# Pipa_PRD.net
KiCad netlist of a schematic drawn in Altium Designer
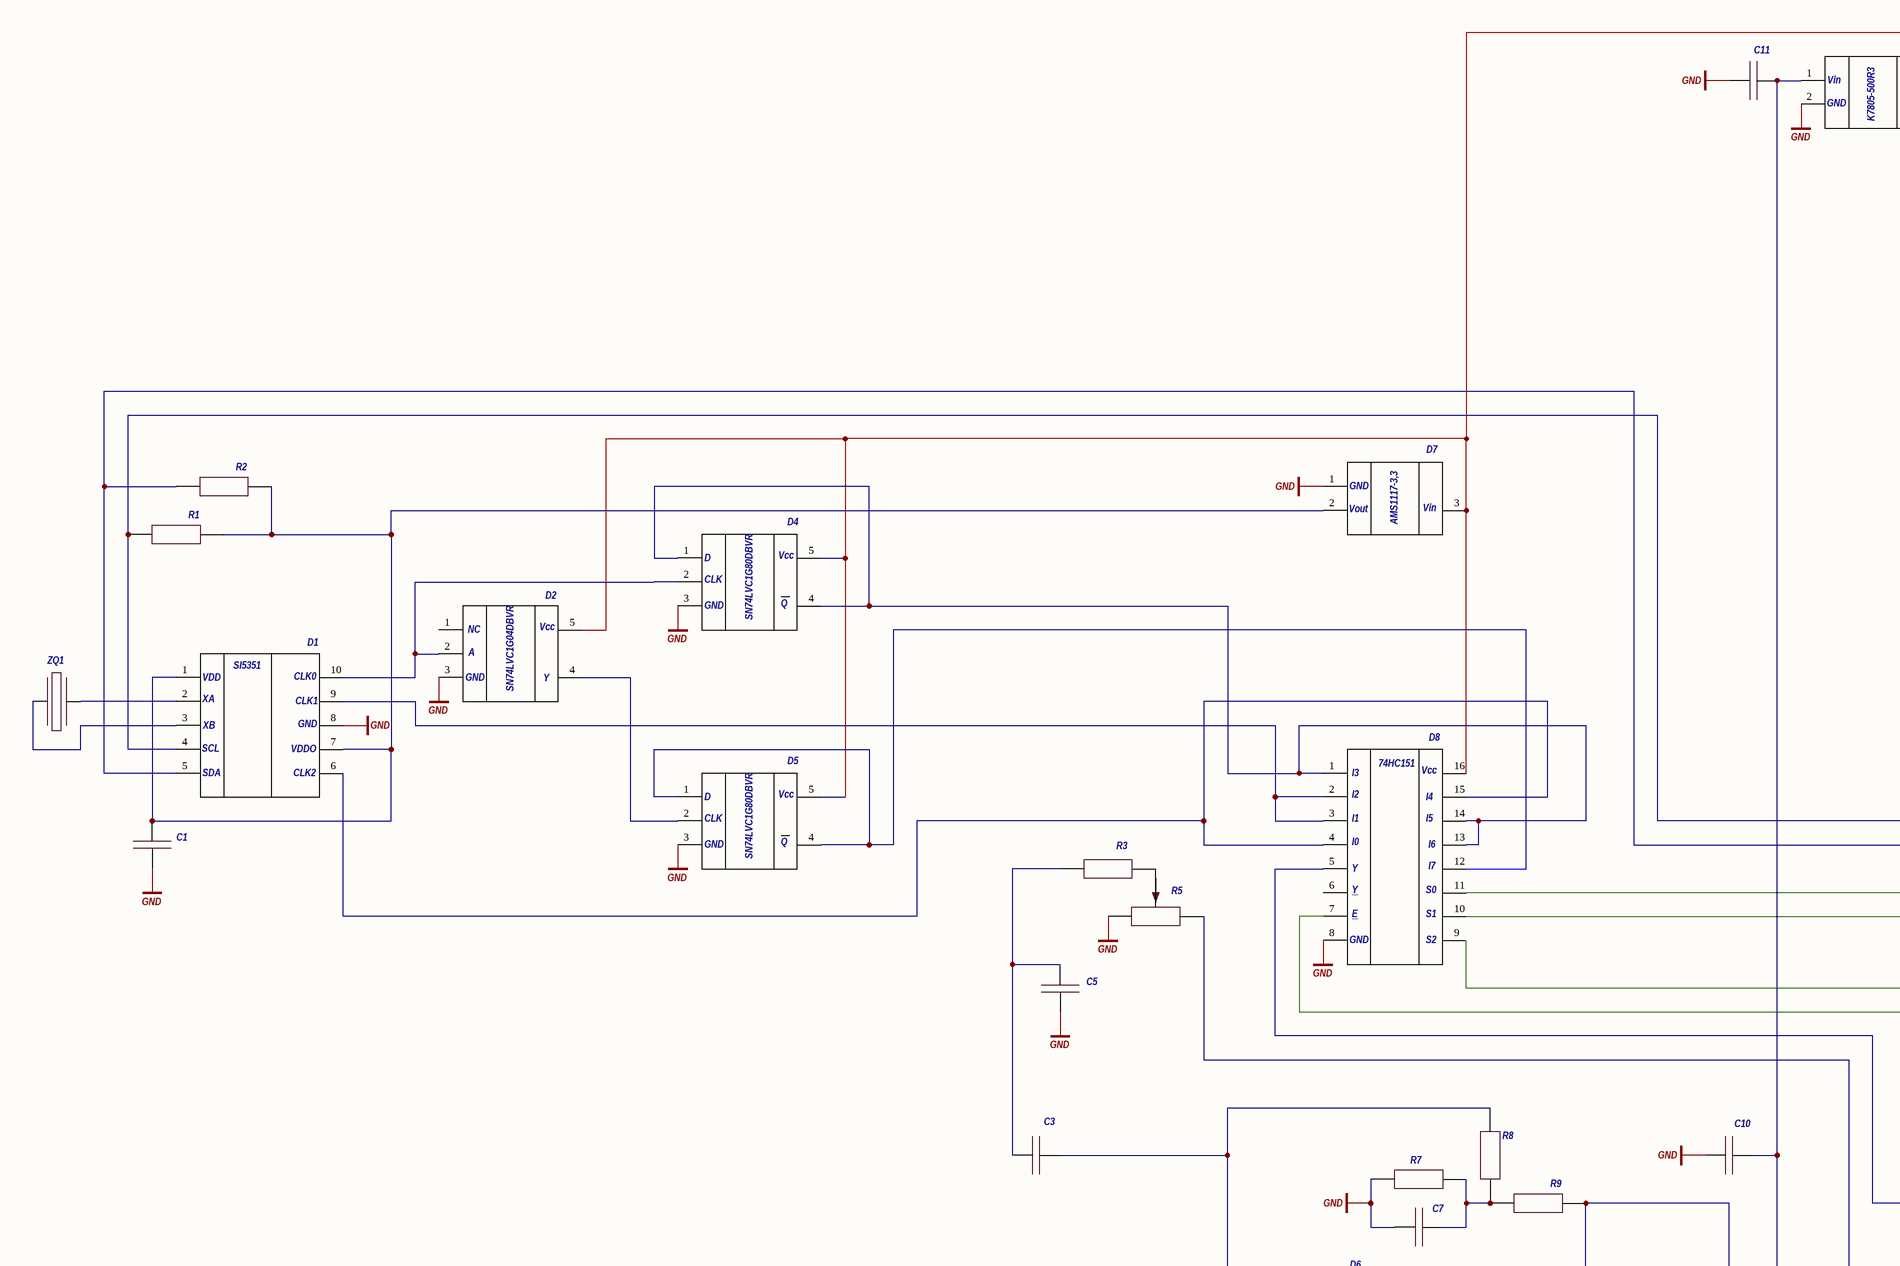
[diagram p0: Pipa PRD.SchDoc, top left]
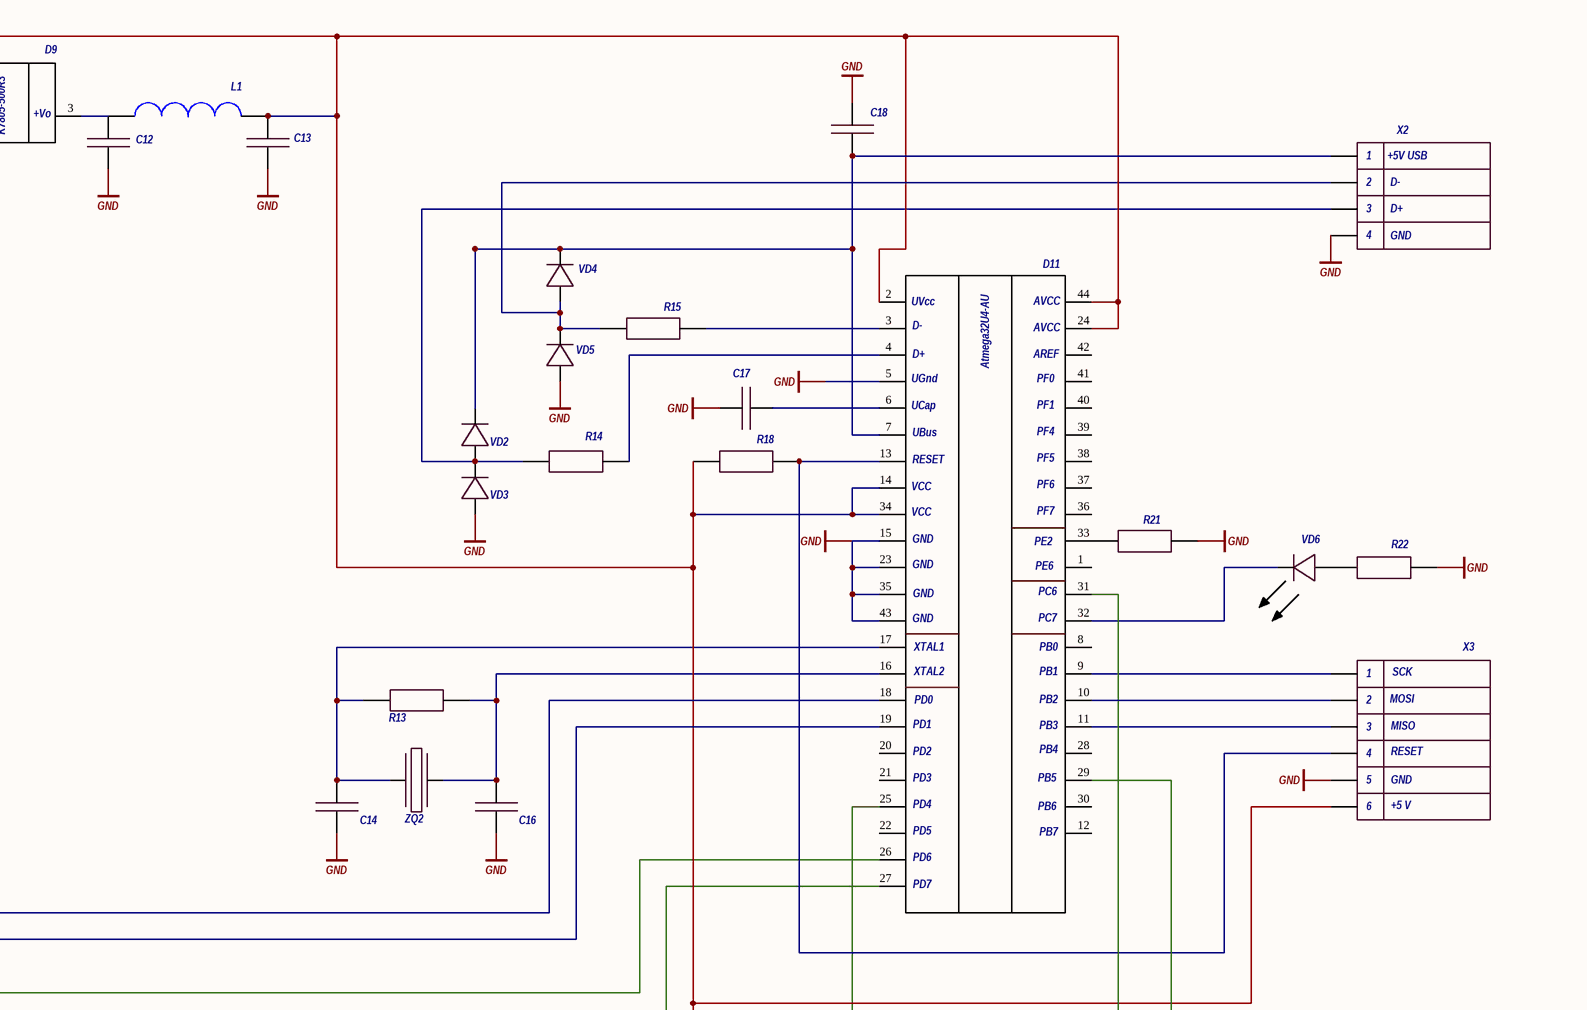
[diagram p1: Pipa PRD.SchDoc, top right]
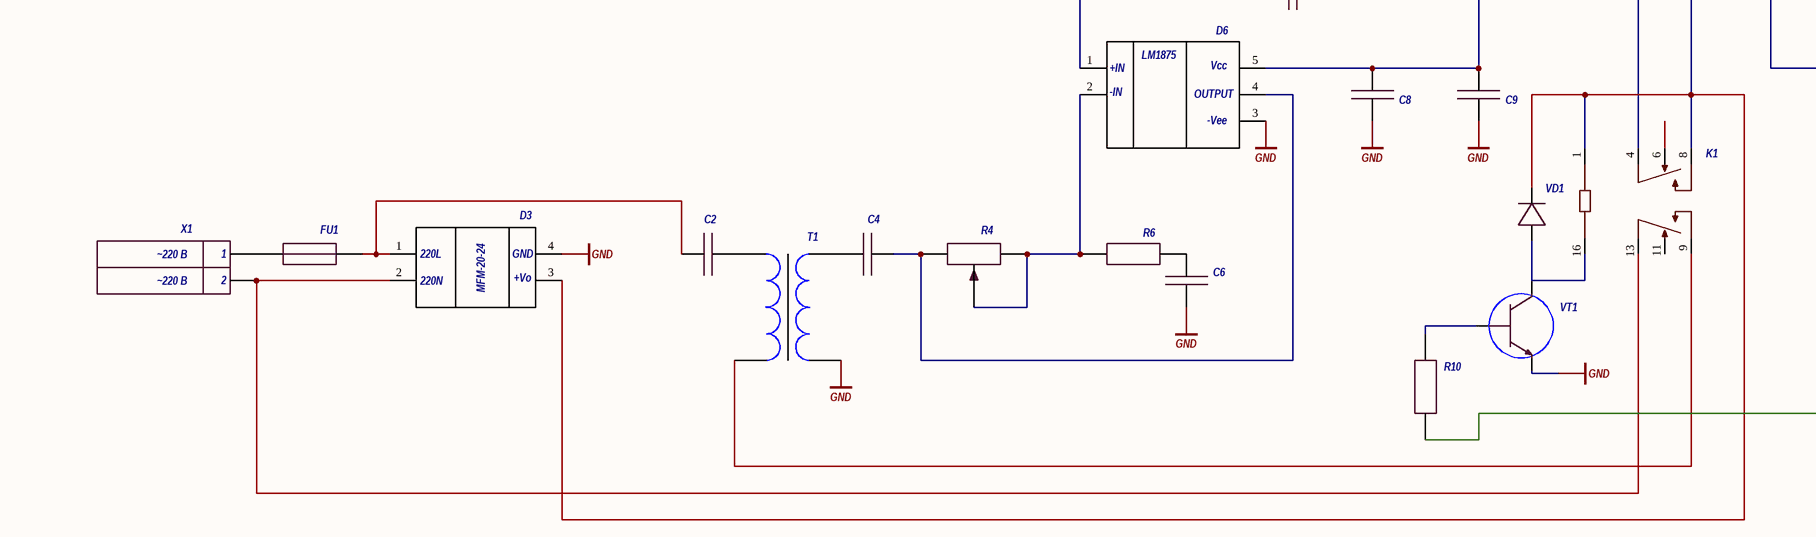
[diagram p2: Pipa PRD.SchDoc, bottom left]
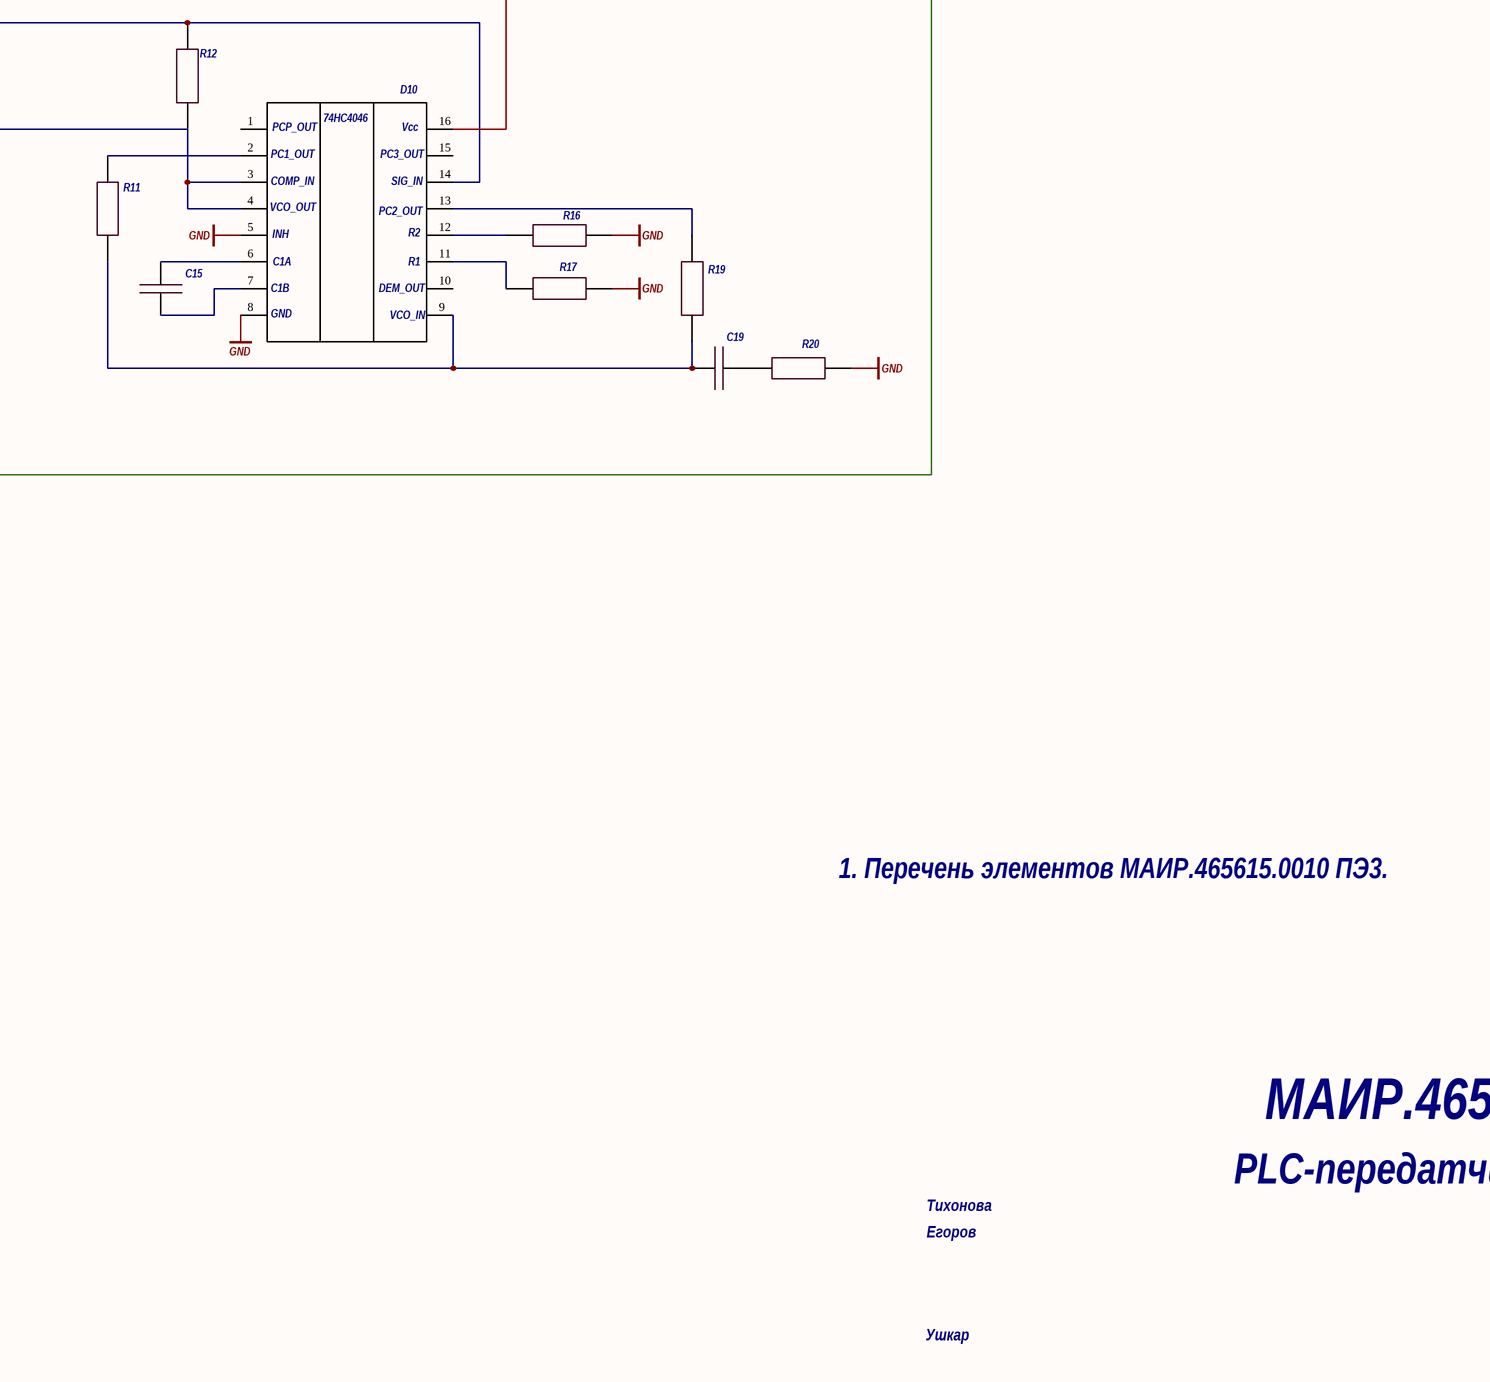
[diagram p3: Pipa PRD.SchDoc, bottom right]

(export (version "E")
  (design (tool "Eeschema 10.0.6"))
  (components
    (comp (ref "C1")
      (value "Конденсатор")
      (footprint "Chokochillipcb:С_0805")
      (libsource (lib "diplom_schlib") (part "Конденсатор"))
    )
    (comp (ref "C2")
      (value "Конденсатор")
      (footprint "Chokochillipcb:C_К73-17 24x11x24")
      (libsource (lib "diplom_schlib") (part "Конденсатор"))
    )
    (comp (ref "C3")
      (value "22 мкФ")
      (footprint "Chokochillipcb:С_0805")
      (libsource (lib "Chokochillisch") (part "Конденсатор"))
    )
    (comp (ref "C4")
      (value "Конденсатор")
      (footprint "Chokochillipcb:С_0805")
      (libsource (lib "diplom_schlib") (part "Конденсатор"))
    )
    (comp (ref "C5")
      (value "Конденсатор")
      (footprint "Chokochillipcb:С_0805")
      (libsource (lib "diplom_schlib") (part "Конденсатор"))
    )
    (comp (ref "C6")
      (value "Конденсатор")
      (footprint "Chokochillipcb:С_0805")
      (libsource (lib "diplom_schlib") (part "Конденсатор"))
    )
    (comp (ref "C7")
      (value "Конденсатор")
      (footprint "Chokochillipcb:С_0805")
      (libsource (lib "diplom_schlib") (part "Конденсатор"))
    )
    (comp (ref "C8")
      (value "Конденсатор")
      (footprint "Chokochillipcb:С_0805")
      (libsource (lib "diplom_schlib") (part "Конденсатор"))
    )
    (comp (ref "C9")
      (value "Конденсатор")
      (footprint "Chokochillipcb:C_К50-35 8x16")
      (libsource (lib "diplom_schlib") (part "Конденсатор"))
    )
    (comp (ref "C10")
      (value "Конденсатор")
      (footprint "Chokochillipcb:C_К50-35 8x16")
      (libsource (lib "Chokochillisch") (part "Конденсатор"))
    )
    (comp (ref "C11")
      (value "Конденсатор")
      (footprint "Chokochillipcb:С_0805")
      (libsource (lib "Chokochillisch") (part "Конденсатор"))
    )
    (comp (ref "C12")
      (value "Конденсатор")
      (footprint "Chokochillipcb:С_0805")
      (libsource (lib "Chokochillisch") (part "Конденсатор"))
    )
    (comp (ref "C13")
      (value "Конденсатор")
      (footprint "Chokochillipcb:C_1206")
      (libsource (lib "Chokochillisch") (part "Конденсатор"))
    )
    (comp (ref "C14")
      (value "Конденсатор")
      (footprint "Chokochillipcb:С_0805")
      (libsource (lib "Chokochillisch") (part "Конденсатор"))
    )
    (comp (ref "C15")
      (value "Конденсатор")
      (footprint "Chokochillipcb:С_0805")
      (libsource (lib "diplom_schlib") (part "Конденсатор"))
    )
    (comp (ref "C16")
      (value "Конденсатор")
      (footprint "Chokochillipcb:С_0805")
      (libsource (lib "Chokochillisch") (part "Конденсатор"))
    )
    (comp (ref "C17")
      (value "Конденсатор")
      (footprint "Chokochillipcb:С_0805")
      (libsource (lib "Chokochillisch") (part "Конденсатор"))
    )
    (comp (ref "C18")
      (value "Конденсатор")
      (footprint "Chokochillipcb:С_0805")
      (libsource (lib "Chokochillisch") (part "Конденсатор"))
    )
    (comp (ref "C19")
      (value "Конденсатор")
      (footprint "Chokochillipcb:С_0805")
      (libsource (lib "diplom_schlib") (part "Конденсатор"))
    )
    (comp (ref "D1")
      (value "Микросхема SI5351")
      (footprint "Chokochillipcb:MSOP-10")
      (libsource (lib "diplom_schlib") (part "Микросхема SI5351"))
    )
    (comp (ref "D2")
      (value "Микросхема SN74LVC1G04DBVR")
      (footprint "Chokochillipcb:SOT-23-5 (3D)")
      (libsource (lib "Chokochillisch") (part "Микросхема SN74LVC1G04DBVR"))
    )
    (comp (ref "D3")
      (value "MFM-20-24 преобразователь")
      (footprint "Chokochillipcb:MFM-20-24 (3D)")
      (libsource (lib "Chokochillisch") (part "MFM-20-24 преобразователь"))
    )
    (comp (ref "D4")
      (value "Микросхема SN74LVC1G80DBVR")
      (footprint "Chokochillipcb:SOT-23-5 (3D)")
      (libsource (lib "Chokochillisch") (part "Микросхема SN74LVC1G80DBVR"))
    )
    (comp (ref "D5")
      (value "Микросхема SN74LVC1G80DBVR")
      (footprint "Chokochillipcb:SOT-23-5 (3D)")
      (libsource (lib "Chokochillisch") (part "Микросхема SN74LVC1G80DBVR"))
    )
    (comp (ref "D6")
      (value "Микросхема LM1875")
      (footprint "Chokochillipcb:TO-220-5")
      (libsource (lib "diplom_schlib") (part "Микросхема LM1875"))
    )
    (comp (ref "D7")
      (value "Микросхема AMS1117-3,3")
      (footprint "Chokochillipcb:SOT-223")
      (libsource (lib "diplom_schlib") (part "Микросхема AMS1117-3,3"))
    )
    (comp (ref "D8")
      (value "Микросхема 74НС151")
      (footprint "Chokochillipcb:SO16")
      (libsource (lib "diplom_schlib") (part "Микросхема 74НС151"))
    )
    (comp (ref "D9")
      (value "Микросхема K7805-500R3")
      (footprint "Chokochillipcb:K7805-500R3 (3D)")
      (libsource (lib "Chokochillisch") (part "Микросхема K7805-500R3"))
    )
    (comp (ref "D10")
      (value "D")
      (footprint "Chokochillipcb:SOIC-16 (3D)")
      (libsource (lib "diplom_schlib") (part "Микросхема 74НС4046"))
    )
    (comp (ref "D11")
      (value "Микросхема ATmega32U4-AU")
      (footprint "Chokochillipcb:TQFP-44 (3D)")
      (libsource (lib "Chokochillisch") (part "Микросхема ATmega32U4-AU"))
    )
    (comp (ref "FU1")
      (value "Предохранитель")
      (footprint "Chokochillipcb:FU_H520PT")
      (libsource (lib "diplom_schlib") (part "Предохранитель"))
    )
    (comp (ref "K1")
      (value "Реле HJR1-2C")
      (footprint "Chokochillipcb:HJR1-2C")
      (libsource (lib "Chokochillisch") (part "Реле HJR1-2C"))
    )
    (comp (ref "L1")
      (value "Катушка индуктивности")
      (footprint "Chokochillipcb:L_1812")
      (libsource (lib "Chokochillisch") (part "Катушка индуктивности"))
    )
    (comp (ref "R1")
      (value "Резистор")
      (footprint "Chokochillipcb:R_0805")
      (libsource (lib "diplom_schlib") (part "Резистор"))
    )
    (comp (ref "R2")
      (value "Резистор")
      (footprint "Chokochillipcb:R_0805")
      (libsource (lib "diplom_schlib") (part "Резистор"))
    )
    (comp (ref "R3")
      (value "Резистор")
      (footprint "Chokochillipcb:R_0805")
      (libsource (lib "diplom_schlib") (part "Резистор"))
    )
    (comp (ref "R4")
      (value "100 k")
      (footprint "Chokochillipcb:3362P")
      (libsource (lib "diplom_schlib") (part "Потенциометр"))
    )
    (comp (ref "R5")
      (value "1 кОм")
      (footprint "Chokochillipcb:3362P")
      (libsource (lib "Chokochillisch") (part "Потенциометр"))
    )
    (comp (ref "R6")
      (value "Резистор")
      (footprint "Chokochillipcb:R_0805")
      (libsource (lib "diplom_schlib") (part "Резистор"))
    )
    (comp (ref "R7")
      (value "Резистор")
      (footprint "Chokochillipcb:R_0805")
      (libsource (lib "diplom_schlib") (part "Резистор"))
    )
    (comp (ref "R8")
      (value "Резистор")
      (footprint "Chokochillipcb:R_0805")
      (libsource (lib "diplom_schlib") (part "Резистор"))
    )
    (comp (ref "R9")
      (value "Резистор")
      (footprint "Chokochillipcb:R_0805")
      (libsource (lib "diplom_schlib") (part "Резистор"))
    )
    (comp (ref "R10")
      (value "Резистор")
      (footprint "Chokochillipcb:R_0805")
      (libsource (lib "Chokochillisch") (part "Резистор"))
    )
    (comp (ref "R11")
      (value "Резистор")
      (footprint "Chokochillipcb:R_0805")
      (libsource (lib "diplom_schlib") (part "Резистор"))
    )
    (comp (ref "R12")
      (value "Резистор*")
      (footprint "Chokochillipcb:R_0805")
      (libsource (lib "Chokochillisch") (part "Резистор"))
    )
    (comp (ref "R13")
      (value "Резистор")
      (footprint "Chokochillipcb:R_0805")
      (libsource (lib "Chokochillisch") (part "Резистор"))
    )
    (comp (ref "R14")
      (value "Резистор")
      (footprint "Chokochillipcb:R_0805")
      (libsource (lib "Chokochillisch") (part "Резистор"))
    )
    (comp (ref "R15")
      (value "Резистор")
      (footprint "Chokochillipcb:R_0805")
      (libsource (lib "Chokochillisch") (part "Резистор"))
    )
    (comp (ref "R16")
      (value "Резистор")
      (footprint "Chokochillipcb:R_0805")
      (libsource (lib "diplom_schlib") (part "Резистор"))
    )
    (comp (ref "R17")
      (value "Резистор")
      (footprint "Chokochillipcb:R_0805")
      (libsource (lib "diplom_schlib") (part "Резистор"))
    )
    (comp (ref "R18")
      (value "Резистор")
      (footprint "Chokochillipcb:R_0805")
      (libsource (lib "Chokochillisch") (part "Резистор"))
    )
    (comp (ref "R19")
      (value "Резистор")
      (footprint "Chokochillipcb:R_0805")
      (libsource (lib "diplom_schlib") (part "Резистор"))
    )
    (comp (ref "R20")
      (value "Резистор")
      (footprint "Chokochillipcb:R_0805")
      (libsource (lib "Chokochillisch") (part "Резистор"))
    )
    (comp (ref "R21")
      (value "Резистор")
      (footprint "Chokochillipcb:R_0805")
      (libsource (lib "Chokochillisch") (part "Резистор"))
    )
    (comp (ref "R22")
      (value "Резистор")
      (footprint "Chokochillipcb:R_0805")
      (libsource (lib "Chokochillisch") (part "Резистор"))
    )
    (comp (ref "T1")
      (value "Трансформатор 4 вывода")
      (footprint "Chokochillipcb:B82790")
      (libsource (lib "diplom_schlib") (part "Трансформатор 4 вывода"))
    )
    (comp (ref "VD1")
      (value "Диод")
      (footprint "Chokochillipcb:SOT-23-3 (3D)")
      (libsource (lib "Chokochillisch") (part "Диод"))
    )
    (comp (ref "VD2")
      (value "Диод")
      (footprint "Chokochillipcb:SOD-323")
      (libsource (lib "Chokochillisch") (part "Диод"))
    )
    (comp (ref "VD3")
      (value "Диод")
      (footprint "Chokochillipcb:SOD-323")
      (libsource (lib "Chokochillisch") (part "Диод"))
    )
    (comp (ref "VD4")
      (value "Диод")
      (footprint "Chokochillipcb:SOD-323")
      (libsource (lib "Chokochillisch") (part "Диод"))
    )
    (comp (ref "VD5")
      (value "Диод")
      (footprint "Chokochillipcb:SOD-323")
      (libsource (lib "Chokochillisch") (part "Диод"))
    )
    (comp (ref "VD6")
      (value "Светодиод")
      (footprint "Chokochillipcb:VD_0805 SMD LED RED")
      (libsource (lib "Chokochillisch") (part "Светодиод"))
    )
    (comp (ref "VT1")
      (value "Транзистор n-p-n")
      (footprint "Chokochillipcb:SOT-23-3 (3D)")
      (libsource (lib "Chokochillisch") (part "Транзистор n-p-n"))
    )
    (comp (ref "X1")
      (value "Разъём 2 пин")
      (footprint "Chokochillipcb:X_WJ126-5")
      (libsource (lib "diplom_schlib") (part "Разъём 2 пин"))
    )
    (comp (ref "X2")
      (value "Разъём 4 пин")
      (footprint "Chokochillipcb:UCB-B (3D)")
      (libsource (lib "Chokochillisch") (part "Разъём 4 пин"))
    )
    (comp (ref "X3")
      (value "Разъём 6 пин")
      (footprint "Chokochillipcb:X-PLS-6")
      (libsource (lib "Chokochillisch") (part "Разъём 6 пин"))
    )
    (comp (ref "ZQ1")
      (value "Резонатор")
      (footprint "Chokochillipcb:HC33U")
      (libsource (lib "diplom_schlib") (part "Резонатор"))
    )
    (comp (ref "ZQ2")
      (value "Резонатор")
      (footprint "Chokochillipcb:HC49S")
      (libsource (lib "Chokochillisch") (part "Резонатор"))
    )
  )
  (nets
    (net (code "1") (name "GND") (class "Default")
      (node (ref "C1") (pin "2") (pinfunction "2_2") (pintype "passive"))
      (node (ref "C10") (pin "2") (pinfunction "2_2") (pintype "passive"))
      (node (ref "C11") (pin "1") (pinfunction "1_1") (pintype "passive"))
      (node (ref "C12") (pin "1") (pinfunction "1_1") (pintype "passive"))
      (node (ref "C13") (pin "1") (pinfunction "1_1") (pintype "passive"))
      (node (ref "C14") (pin "1") (pinfunction "1_1") (pintype "passive"))
      (node (ref "C16") (pin "1") (pinfunction "1_1") (pintype "passive"))
      (node (ref "C17") (pin "2") (pinfunction "2_2") (pintype "passive"))
      (node (ref "C18") (pin "2") (pinfunction "2_2") (pintype "passive"))
      (node (ref "C5") (pin "1") (pinfunction "1_1") (pintype "passive"))
      (node (ref "C6") (pin "1") (pinfunction "1_1") (pintype "passive"))
      (node (ref "C7") (pin "1") (pinfunction "1_1") (pintype "passive"))
      (node (ref "C8") (pin "2") (pinfunction "2_2") (pintype "passive"))
      (node (ref "C9") (pin "1") (pinfunction "1_1") (pintype "passive"))
      (node (ref "D1") (pin "8") (pinfunction "8_8") (pintype "passive"))
      (node (ref "D10") (pin "5") (pinfunction "5_5") (pintype "passive"))
      (node (ref "D10") (pin "8") (pinfunction "8_8") (pintype "passive"))
      (node (ref "D11") (pin "15") (pinfunction "15_15") (pintype "passive"))
      (node (ref "D11") (pin "23") (pinfunction "23_23") (pintype "passive"))
      (node (ref "D11") (pin "35") (pinfunction "35_35") (pintype "passive"))
      (node (ref "D11") (pin "43") (pinfunction "43_43") (pintype "passive"))
      (node (ref "D11") (pin "5") (pinfunction "5_5") (pintype "passive"))
      (node (ref "D2") (pin "3") (pinfunction "3_3") (pintype "passive"))
      (node (ref "D3") (pin "4") (pinfunction "4_4") (pintype "passive"))
      (node (ref "D4") (pin "3") (pinfunction "3_3") (pintype "passive"))
      (node (ref "D5") (pin "3") (pinfunction "3_3") (pintype "passive"))
      (node (ref "D6") (pin "3") (pinfunction "3_3") (pintype "passive"))
      (node (ref "D7") (pin "1") (pinfunction "1_1") (pintype "passive"))
      (node (ref "D8") (pin "8") (pinfunction "8_8") (pintype "passive"))
      (node (ref "D9") (pin "2") (pinfunction "2_2") (pintype "passive"))
      (node (ref "R16") (pin "2") (pinfunction "2_2") (pintype "passive"))
      (node (ref "R17") (pin "2") (pinfunction "2_2") (pintype "passive"))
      (node (ref "R20") (pin "1") (pinfunction "1_1") (pintype "passive"))
      (node (ref "R21") (pin "2") (pinfunction "2_2") (pintype "passive"))
      (node (ref "R22") (pin "2") (pinfunction "2_2") (pintype "passive"))
      (node (ref "R5") (pin "1") (pinfunction "1_1") (pintype "passive"))
      (node (ref "R7") (pin "2") (pinfunction "2_2") (pintype "passive"))
      (node (ref "T1") (pin "3") (pinfunction "3_3") (pintype "passive"))
      (node (ref "VD3") (pin "1") (pinfunction "1_1") (pintype "passive"))
      (node (ref "VD5") (pin "1") (pinfunction "1_1") (pintype "passive"))
      (node (ref "VT1") (pin "1") (pinfunction "1_1") (pintype "passive"))
      (node (ref "X2") (pin "4") (pinfunction "4_4") (pintype "passive"))
      (node (ref "X3") (pin "5") (pinfunction "5_5") (pintype "passive"))
    )
    (net (code "2") (name "Net-(C1-Pad1)") (class "Default")
      (node (ref "C1") (pin "1") (pinfunction "1_1") (pintype "passive"))
      (node (ref "D1") (pin "1") (pinfunction "1_1") (pintype "passive"))
      (node (ref "D1") (pin "7") (pinfunction "7_7") (pintype "passive"))
      (node (ref "D7") (pin "2") (pinfunction "2_2") (pintype "passive"))
      (node (ref "R1") (pin "1") (pinfunction "1_1") (pintype "passive"))
      (node (ref "R2") (pin "1") (pinfunction "1_1") (pintype "passive"))
    )
    (net (code "3") (name "Net-(C2-Pad1)") (class "Default")
      (node (ref "C2") (pin "1") (pinfunction "1_1") (pintype "passive"))
      (node (ref "T1") (pin "1") (pinfunction "1_1") (pintype "passive"))
    )
    (net (code "4") (name "Net-(C2-Pad2)") (class "Default")
      (node (ref "C2") (pin "2") (pinfunction "2_2") (pintype "passive"))
      (node (ref "D3") (pin "1") (pinfunction "1_1") (pintype "passive"))
      (node (ref "FU1") (pin "2") (pinfunction "2_2") (pintype "passive"))
    )
    (net (code "5") (name "Net-(C3-Pad1)") (class "Default")
      (node (ref "C3") (pin "1") (pinfunction "1_1") (pintype "passive"))
      (node (ref "D6") (pin "1") (pinfunction "1_1") (pintype "passive"))
      (node (ref "R8") (pin "2") (pinfunction "2_2") (pintype "passive"))
    )
    (net (code "6") (name "Net-(C3-Pad2)") (class "Default")
      (node (ref "C3") (pin "2") (pinfunction "2_2") (pintype "passive"))
      (node (ref "C5") (pin "2") (pinfunction "2_2") (pintype "passive"))
      (node (ref "R3") (pin "2") (pinfunction "2_2") (pintype "passive"))
    )
    (net (code "7") (name "Net-(C4-Pad1)") (class "Default")
      (node (ref "C4") (pin "1") (pinfunction "1_1") (pintype "passive"))
      (node (ref "T1") (pin "4") (pinfunction "4_4") (pintype "passive"))
    )
    (net (code "8") (name "Net-(C4-Pad2)") (class "Default")
      (node (ref "C4") (pin "2") (pinfunction "2_2") (pintype "passive"))
      (node (ref "D6") (pin "4") (pinfunction "4_4") (pintype "passive"))
      (node (ref "R4") (pin "2") (pinfunction "2_2") (pintype "passive"))
    )
    (net (code "9") (name "Net-(C6-Pad2)") (class "Default")
      (node (ref "C6") (pin "2") (pinfunction "2_2") (pintype "passive"))
      (node (ref "R6") (pin "2") (pinfunction "2_2") (pintype "passive"))
    )
    (net (code "10") (name "Net-(C7-Pad2)") (class "Default")
      (node (ref "C7") (pin "2") (pinfunction "2_2") (pintype "passive"))
      (node (ref "R7") (pin "1") (pinfunction "1_1") (pintype "passive"))
      (node (ref "R8") (pin "1") (pinfunction "1_1") (pintype "passive"))
      (node (ref "R9") (pin "1") (pinfunction "1_1") (pintype "passive"))
    )
    (net (code "11") (name "Net-(C8-Pad1)") (class "Default")
      (node (ref "C8") (pin "1") (pinfunction "1_1") (pintype "passive"))
      (node (ref "C9") (pin "2") (pinfunction "2_2") (pintype "passive"))
      (node (ref "D6") (pin "5") (pinfunction "5_5") (pintype "passive"))
      (node (ref "K1") (pin "4") (pinfunction "4_4") (pintype "passive"))
      (node (ref "R9") (pin "2") (pinfunction "2_2") (pintype "passive"))
    )
    (net (code "12") (name "Net-(C10-Pad1)") (class "Default")
      (node (ref "C10") (pin "1") (pinfunction "1_1") (pintype "passive"))
      (node (ref "C11") (pin "2") (pinfunction "2_2") (pintype "passive"))
      (node (ref "D3") (pin "3") (pinfunction "3_3") (pintype "passive"))
      (node (ref "D9") (pin "1") (pinfunction "1_1") (pintype "passive"))
      (node (ref "K1") (pin "1") (pinfunction "1_1") (pintype "passive"))
      (node (ref "K1") (pin "8") (pinfunction "8_8") (pintype "passive"))
      (node (ref "VD1") (pin "2") (pinfunction "2_2") (pintype "passive"))
    )
    (net (code "13") (name "Net-(C12-Pad2)") (class "Default")
      (node (ref "C12") (pin "2") (pinfunction "2_2") (pintype "passive"))
      (node (ref "D9") (pin "3") (pinfunction "3_3") (pintype "passive"))
      (node (ref "L1") (pin "1") (pinfunction "1_1") (pintype "passive"))
    )
    (net (code "14") (name "Net-(C13-Pad2)") (class "Default")
      (node (ref "C13") (pin "2") (pinfunction "2_2") (pintype "passive"))
      (node (ref "D10") (pin "16") (pinfunction "16_16") (pintype "passive"))
      (node (ref "D11") (pin "14") (pinfunction "14_14") (pintype "passive"))
      (node (ref "D11") (pin "2") (pinfunction "2_2") (pintype "passive"))
      (node (ref "D11") (pin "24") (pinfunction "24_24") (pintype "passive"))
      (node (ref "D11") (pin "34") (pinfunction "34_34") (pintype "passive"))
      (node (ref "D11") (pin "44") (pinfunction "44_44") (pintype "passive"))
      (node (ref "D2") (pin "5") (pinfunction "5_5") (pintype "passive"))
      (node (ref "D4") (pin "5") (pinfunction "5_5") (pintype "passive"))
      (node (ref "D5") (pin "5") (pinfunction "5_5") (pintype "passive"))
      (node (ref "D7") (pin "3") (pinfunction "3_3") (pintype "passive"))
      (node (ref "D8") (pin "16") (pinfunction "16_16") (pintype "passive"))
      (node (ref "L1") (pin "2") (pinfunction "2_2") (pintype "passive"))
      (node (ref "R18") (pin "2") (pinfunction "2_2") (pintype "passive"))
      (node (ref "X3") (pin "6") (pinfunction "6_6") (pintype "passive"))
    )
    (net (code "15") (name "Net-(C14-Pad2)") (class "Default")
      (node (ref "C14") (pin "2") (pinfunction "2_2") (pintype "passive"))
      (node (ref "D11") (pin "17") (pinfunction "17_17") (pintype "passive"))
      (node (ref "R13") (pin "1") (pinfunction "1_1") (pintype "passive"))
      (node (ref "ZQ2") (pin "1") (pinfunction "1_1") (pintype "passive"))
    )
    (net (code "16") (name "Net-(C15-Pad1)") (class "Default")
      (node (ref "C15") (pin "1") (pinfunction "1_1") (pintype "passive"))
      (node (ref "D10") (pin "7") (pinfunction "7_7") (pintype "passive"))
    )
    (net (code "17") (name "Net-(C15-Pad2)") (class "Default")
      (node (ref "C15") (pin "2") (pinfunction "2_2") (pintype "passive"))
      (node (ref "D10") (pin "6") (pinfunction "6_6") (pintype "passive"))
    )
    (net (code "18") (name "Net-(C16-Pad2)") (class "Default")
      (node (ref "C16") (pin "2") (pinfunction "2_2") (pintype "passive"))
      (node (ref "D11") (pin "16") (pinfunction "16_16") (pintype "passive"))
      (node (ref "R13") (pin "2") (pinfunction "2_2") (pintype "passive"))
      (node (ref "ZQ2") (pin "2") (pinfunction "2_2") (pintype "passive"))
    )
    (net (code "19") (name "Net-(C17-Pad1)") (class "Default")
      (node (ref "C17") (pin "1") (pinfunction "1_1") (pintype "passive"))
      (node (ref "D11") (pin "6") (pinfunction "6_6") (pintype "passive"))
    )
    (net (code "20") (name "Net-(C18-Pad1)") (class "Default")
      (node (ref "C18") (pin "1") (pinfunction "1_1") (pintype "passive"))
      (node (ref "D11") (pin "7") (pinfunction "7_7") (pintype "passive"))
      (node (ref "VD2") (pin "2") (pinfunction "2_2") (pintype "passive"))
      (node (ref "VD4") (pin "2") (pinfunction "2_2") (pintype "passive"))
      (node (ref "X2") (pin "1") (pinfunction "1_1") (pintype "passive"))
    )
    (net (code "21") (name "Net-(C19-Pad1)") (class "Default")
      (node (ref "C19") (pin "1") (pinfunction "1_1") (pintype "passive"))
      (node (ref "D10") (pin "9") (pinfunction "9_9") (pintype "passive"))
      (node (ref "R11") (pin "2") (pinfunction "2_2") (pintype "passive"))
      (node (ref "R19") (pin "1") (pinfunction "1_1") (pintype "passive"))
    )
    (net (code "22") (name "Net-(C19-Pad2)") (class "Default")
      (node (ref "C19") (pin "2") (pinfunction "2_2") (pintype "passive"))
      (node (ref "R20") (pin "2") (pinfunction "2_2") (pintype "passive"))
    )
    (net (code "23") (name "Net-(D1-Pad2)") (class "Default")
      (node (ref "D1") (pin "2") (pinfunction "2_2") (pintype "passive"))
      (node (ref "ZQ1") (pin "2") (pinfunction "2_2") (pintype "passive"))
    )
    (net (code "24") (name "Net-(D1-Pad3)") (class "Default")
      (node (ref "D1") (pin "3") (pinfunction "3_3") (pintype "passive"))
      (node (ref "ZQ1") (pin "1") (pinfunction "1_1") (pintype "passive"))
    )
    (net (code "25") (name "Net-(D1-Pad4)") (class "Default")
      (node (ref "D1") (pin "4") (pinfunction "4_4") (pintype "passive"))
      (node (ref "D11") (pin "18") (pinfunction "18_18") (pintype "passive"))
      (node (ref "R1") (pin "2") (pinfunction "2_2") (pintype "passive"))
    )
    (net (code "26") (name "Net-(D1-Pad5)") (class "Default")
      (node (ref "D1") (pin "5") (pinfunction "5_5") (pintype "passive"))
      (node (ref "D11") (pin "19") (pinfunction "19_19") (pintype "passive"))
      (node (ref "R2") (pin "2") (pinfunction "2_2") (pintype "passive"))
    )
    (net (code "27") (name "Net-(D1-Pad6)") (class "Default")
      (node (ref "D1") (pin "6") (pinfunction "6_6") (pintype "passive"))
      (node (ref "D8") (pin "15") (pinfunction "15_15") (pintype "passive"))
      (node (ref "D8") (pin "4") (pinfunction "4_4") (pintype "passive"))
    )
    (net (code "28") (name "Net-(D1-Pad9)") (class "Default")
      (node (ref "D1") (pin "9") (pinfunction "9_9") (pintype "passive"))
      (node (ref "D8") (pin "2") (pinfunction "2_2") (pintype "passive"))
      (node (ref "D8") (pin "3") (pinfunction "3_3") (pintype "passive"))
    )
    (net (code "29") (name "Net-(D1-Pad10)") (class "Default")
      (node (ref "D1") (pin "10") (pinfunction "10_10") (pintype "passive"))
      (node (ref "D2") (pin "2") (pinfunction "2_2") (pintype "passive"))
      (node (ref "D4") (pin "2") (pinfunction "2_2") (pintype "passive"))
    )
    (net (code "30") (name "Net-(D2-Pad4)") (class "Default")
      (node (ref "D2") (pin "4") (pinfunction "4_4") (pintype "passive"))
      (node (ref "D5") (pin "2") (pinfunction "2_2") (pintype "passive"))
    )
    (net (code "31") (name "Net-(D3-Pad2)") (class "Default")
      (node (ref "D3") (pin "2") (pinfunction "2_2") (pintype "passive"))
      (node (ref "K1") (pin "13") (pinfunction "13_13") (pintype "passive"))
      (node (ref "X1") (pin "2") (pinfunction "2_2") (pintype "passive"))
    )
    (net (code "32") (name "Net-(D4-Pad1)") (class "Default")
      (node (ref "D4") (pin "1") (pinfunction "1_1") (pintype "passive"))
      (node (ref "D4") (pin "4") (pinfunction "4_4") (pintype "passive"))
      (node (ref "D8") (pin "1") (pinfunction "1_1") (pintype "passive"))
      (node (ref "D8") (pin "13") (pinfunction "13_13") (pintype "passive"))
      (node (ref "D8") (pin "14") (pinfunction "14_14") (pintype "passive"))
    )
    (net (code "33") (name "Net-(D5-Pad1)") (class "Default")
      (node (ref "D5") (pin "1") (pinfunction "1_1") (pintype "passive"))
      (node (ref "D5") (pin "4") (pinfunction "4_4") (pintype "passive"))
      (node (ref "D8") (pin "12") (pinfunction "12_12") (pintype "passive"))
    )
    (net (code "34") (name "Net-(D6-Pad2)") (class "Default")
      (node (ref "D6") (pin "2") (pinfunction "2_2") (pintype "passive"))
      (node (ref "R4") (pin "1") (pinfunction "1_1") (pintype "passive"))
      (node (ref "R4") (pin "3") (pinfunction "3_3") (pintype "passive"))
      (node (ref "R6") (pin "1") (pinfunction "1_1") (pintype "passive"))
    )
    (net (code "35") (name "Net-(D10-Pad2)") (class "Default")
      (node (ref "D10") (pin "2") (pinfunction "2_2") (pintype "passive"))
      (node (ref "R11") (pin "1") (pinfunction "1_1") (pintype "passive"))
    )
    (net (code "36") (name "Net-(D10-Pad3)") (class "Default")
      (node (ref "D10") (pin "3") (pinfunction "3_3") (pintype "passive"))
      (node (ref "D10") (pin "4") (pinfunction "4_4") (pintype "passive"))
      (node (ref "R12") (pin "2") (pinfunction "2_2") (pintype "passive"))
      (node (ref "R5") (pin "2") (pinfunction "2_2") (pintype "passive"))
    )
    (net (code "37") (name "Net-(D10-Pad11)") (class "Default")
      (node (ref "D10") (pin "11") (pinfunction "11_11") (pintype "passive"))
      (node (ref "R17") (pin "1") (pinfunction "1_1") (pintype "passive"))
    )
    (net (code "38") (name "Net-(D10-Pad12)") (class "Default")
      (node (ref "D10") (pin "12") (pinfunction "12_12") (pintype "passive"))
      (node (ref "R16") (pin "1") (pinfunction "1_1") (pintype "passive"))
    )
    (net (code "39") (name "Net-(D10-Pad13)") (class "Default")
      (node (ref "D10") (pin "13") (pinfunction "13_13") (pintype "passive"))
      (node (ref "R19") (pin "2") (pinfunction "2_2") (pintype "passive"))
    )
    (net (code "40") (name "Net-(D10-Pad14)") (class "Default")
      (node (ref "D10") (pin "14") (pinfunction "14_14") (pintype "passive"))
      (node (ref "D8") (pin "5") (pinfunction "5_5") (pintype "passive"))
      (node (ref "R12") (pin "1") (pinfunction "1_1") (pintype "passive"))
    )
    (net (code "41") (name "Net-(D11-Pad3)") (class "Default")
      (node (ref "D11") (pin "3") (pinfunction "3_3") (pintype "passive"))
      (node (ref "R15") (pin "2") (pinfunction "2_2") (pintype "passive"))
    )
    (net (code "42") (name "Net-(D11-Pad4)") (class "Default")
      (node (ref "D11") (pin "4") (pinfunction "4_4") (pintype "passive"))
      (node (ref "R14") (pin "2") (pinfunction "2_2") (pintype "passive"))
    )
    (net (code "43") (name "Net-(D11-Pad9)") (class "Default")
      (node (ref "D11") (pin "9") (pinfunction "9_9") (pintype "passive"))
      (node (ref "X3") (pin "1") (pinfunction "1_1") (pintype "passive"))
    )
    (net (code "44") (name "Net-(D11-Pad10)") (class "Default")
      (node (ref "D11") (pin "10") (pinfunction "10_10") (pintype "passive"))
      (node (ref "X3") (pin "2") (pinfunction "2_2") (pintype "passive"))
    )
    (net (code "45") (name "Net-(D11-Pad11)") (class "Default")
      (node (ref "D11") (pin "11") (pinfunction "11_11") (pintype "passive"))
      (node (ref "X3") (pin "3") (pinfunction "3_3") (pintype "passive"))
    )
    (net (code "46") (name "Net-(D11-Pad13)") (class "Default")
      (node (ref "D11") (pin "13") (pinfunction "13_13") (pintype "passive"))
      (node (ref "R18") (pin "1") (pinfunction "1_1") (pintype "passive"))
      (node (ref "X3") (pin "4") (pinfunction "4_4") (pintype "passive"))
    )
    (net (code "47") (name "Net-(D11-Pad25)") (class "Default")
      (node (ref "D11") (pin "25") (pinfunction "25_25") (pintype "passive"))
      (node (ref "D8") (pin "7") (pinfunction "7_7") (pintype "passive"))
    )
    (net (code "48") (name "Net-(D11-Pad26)") (class "Default")
      (node (ref "D11") (pin "26") (pinfunction "26_26") (pintype "passive"))
      (node (ref "D8") (pin "11") (pinfunction "11_11") (pintype "passive"))
    )
    (net (code "49") (name "Net-(D11-Pad27)") (class "Default")
      (node (ref "D11") (pin "27") (pinfunction "27_27") (pintype "passive"))
      (node (ref "D8") (pin "10") (pinfunction "10_10") (pintype "passive"))
    )
    (net (code "50") (name "Net-(D11-Pad29)") (class "Default")
      (node (ref "D11") (pin "29") (pinfunction "29_29") (pintype "passive"))
      (node (ref "D8") (pin "9") (pinfunction "9_9") (pintype "passive"))
    )
    (net (code "51") (name "Net-(D11-Pad31)") (class "Default")
      (node (ref "D11") (pin "31") (pinfunction "31_31") (pintype "passive"))
      (node (ref "R10") (pin "2") (pinfunction "2_2") (pintype "passive"))
    )
    (net (code "52") (name "Net-(D11-Pad32)") (class "Default")
      (node (ref "D11") (pin "32") (pinfunction "32_32") (pintype "passive"))
      (node (ref "VD6") (pin "2") (pinfunction "2_2") (pintype "passive"))
    )
    (net (code "53") (name "Net-(D11-Pad33)") (class "Default")
      (node (ref "D11") (pin "33") (pinfunction "33_33") (pintype "passive"))
      (node (ref "R21") (pin "1") (pinfunction "1_1") (pintype "passive"))
    )
    (net (code "54") (name "Net-(FU1-Pad1)") (class "Default")
      (node (ref "FU1") (pin "1") (pinfunction "1_1") (pintype "passive"))
      (node (ref "X1") (pin "1") (pinfunction "1_1") (pintype "passive"))
    )
    (net (code "55") (name "Net-(K1-Pad9)") (class "Default")
      (node (ref "K1") (pin "9") (pinfunction "9_9") (pintype "passive"))
      (node (ref "T1") (pin "2") (pinfunction "2_2") (pintype "passive"))
    )
    (net (code "56") (name "Net-(K1-Pad16)") (class "Default")
      (node (ref "K1") (pin "16") (pinfunction "16_16") (pintype "passive"))
      (node (ref "VD1") (pin "1") (pinfunction "1_1") (pintype "passive"))
      (node (ref "VT1") (pin "2") (pinfunction "2_2") (pintype "passive"))
    )
    (net (code "57") (name "Net-(R3-Pad1)") (class "Default")
      (node (ref "R3") (pin "1") (pinfunction "1_1") (pintype "passive"))
      (node (ref "R5") (pin "3") (pinfunction "3_3") (pintype "passive"))
    )
    (net (code "58") (name "Net-(R10-Pad1)") (class "Default")
      (node (ref "R10") (pin "1") (pinfunction "1_1") (pintype "passive"))
      (node (ref "VT1") (pin "3") (pinfunction "3_3") (pintype "passive"))
    )
    (net (code "59") (name "Net-(R14-Pad1)") (class "Default")
      (node (ref "R14") (pin "1") (pinfunction "1_1") (pintype "passive"))
      (node (ref "VD2") (pin "1") (pinfunction "1_1") (pintype "passive"))
      (node (ref "VD3") (pin "2") (pinfunction "2_2") (pintype "passive"))
      (node (ref "X2") (pin "3") (pinfunction "3_3") (pintype "passive"))
    )
    (net (code "60") (name "Net-(R15-Pad1)") (class "Default")
      (node (ref "R15") (pin "1") (pinfunction "1_1") (pintype "passive"))
      (node (ref "VD4") (pin "1") (pinfunction "1_1") (pintype "passive"))
      (node (ref "VD5") (pin "2") (pinfunction "2_2") (pintype "passive"))
      (node (ref "X2") (pin "2") (pinfunction "2_2") (pintype "passive"))
    )
    (net (code "61") (name "Net-(R22-Pad1)") (class "Default")
      (node (ref "R22") (pin "1") (pinfunction "1_1") (pintype "passive"))
      (node (ref "VD6") (pin "1") (pinfunction "1_1") (pintype "passive"))
    )
    (net (code "62") (name "unconnected-(D2-Pad1)") (class "Default")
      (node (ref "D2") (pin "1") (pinfunction "1_1") (pintype "passive"))
    )
    (net (code "63") (name "unconnected-(D8-Pad6)") (class "Default")
      (node (ref "D8") (pin "6") (pinfunction "6_6") (pintype "passive"))
    )
    (net (code "64") (name "unconnected-(D10-Pad1)") (class "Default")
      (node (ref "D10") (pin "1") (pinfunction "1_1") (pintype "passive"))
    )
    (net (code "65") (name "unconnected-(D10-Pad10)") (class "Default")
      (node (ref "D10") (pin "10") (pinfunction "10_10") (pintype "passive"))
    )
    (net (code "66") (name "unconnected-(D10-Pad15)") (class "Default")
      (node (ref "D10") (pin "15") (pinfunction "15_15") (pintype "passive"))
    )
    (net (code "67") (name "unconnected-(D11-Pad1)") (class "Default")
      (node (ref "D11") (pin "1") (pinfunction "1_1") (pintype "passive"))
    )
    (net (code "68") (name "unconnected-(D11-Pad8)") (class "Default")
      (node (ref "D11") (pin "8") (pinfunction "8_8") (pintype "passive"))
    )
    (net (code "69") (name "unconnected-(D11-Pad12)") (class "Default")
      (node (ref "D11") (pin "12") (pinfunction "12_12") (pintype "passive"))
    )
    (net (code "70") (name "unconnected-(D11-Pad20)") (class "Default")
      (node (ref "D11") (pin "20") (pinfunction "20_20") (pintype "passive"))
    )
    (net (code "71") (name "unconnected-(D11-Pad21)") (class "Default")
      (node (ref "D11") (pin "21") (pinfunction "21_21") (pintype "passive"))
    )
    (net (code "72") (name "unconnected-(D11-Pad22)") (class "Default")
      (node (ref "D11") (pin "22") (pinfunction "22_22") (pintype "passive"))
    )
    (net (code "73") (name "unconnected-(D11-Pad28)") (class "Default")
      (node (ref "D11") (pin "28") (pinfunction "28_28") (pintype "passive"))
    )
    (net (code "74") (name "unconnected-(D11-Pad30)") (class "Default")
      (node (ref "D11") (pin "30") (pinfunction "30_30") (pintype "passive"))
    )
    (net (code "75") (name "unconnected-(D11-Pad36)") (class "Default")
      (node (ref "D11") (pin "36") (pinfunction "36_36") (pintype "passive"))
    )
    (net (code "76") (name "unconnected-(D11-Pad37)") (class "Default")
      (node (ref "D11") (pin "37") (pinfunction "37_37") (pintype "passive"))
    )
    (net (code "77") (name "unconnected-(D11-Pad38)") (class "Default")
      (node (ref "D11") (pin "38") (pinfunction "38_38") (pintype "passive"))
    )
    (net (code "78") (name "unconnected-(D11-Pad39)") (class "Default")
      (node (ref "D11") (pin "39") (pinfunction "39_39") (pintype "passive"))
    )
    (net (code "79") (name "unconnected-(D11-Pad40)") (class "Default")
      (node (ref "D11") (pin "40") (pinfunction "40_40") (pintype "passive"))
    )
    (net (code "80") (name "unconnected-(D11-Pad41)") (class "Default")
      (node (ref "D11") (pin "41") (pinfunction "41_41") (pintype "passive"))
    )
    (net (code "81") (name "unconnected-(D11-Pad42)") (class "Default")
      (node (ref "D11") (pin "42") (pinfunction "42_42") (pintype "passive"))
    )
    (net (code "82") (name "unconnected-(K1-Pad6)") (class "Default")
      (node (ref "K1") (pin "6") (pinfunction "6_6") (pintype "passive"))
    )
    (net (code "83") (name "unconnected-(K1-Pad11)") (class "Default")
      (node (ref "K1") (pin "11") (pinfunction "11_11") (pintype "passive"))
    )
  )
)
